# Sheet1.net
KiCad netlist of a schematic drawn in Altium Designer
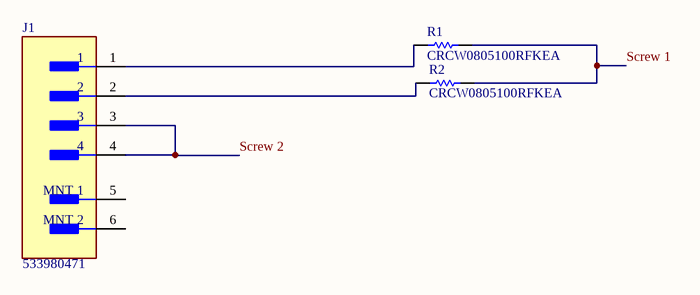
[diagram p0: Sheet1.SchDoc]

(export (version "E")
  (design (tool "Eeschema 10.0.6"))
  (components
    (comp (ref "J1")
      (value "533980471")
      (footprint "FP-533980471-MFG")
      (description "CONN HEADER SMD 4POS 1.25MM")
      (fields
        (field (name "OCTOPART") "https://octopart.com/53398-0471-molex-655296")
        (field (name "MANUFACTURER") "Molex")
      )
      (libsource (lib "Altium Content Vault") (part "3b6f738a5616415d78381ad43816e4a"))
    )
    (comp (ref "R1")
      (value "CRCW0805100RFKEA")
      (footprint "RESC2013X50X30LL20T20")
      (fields (field (name "MANUFACTURER") "Vishay Dale"))
      (libsource (lib "Altium Content Vault") (part "RES"))
    )
    (comp (ref "R2")
      (value "CRCW0805100RFKEA")
      (footprint "RESC2013X50X30LL20T20")
      (fields (field (name "MANUFACTURER") "Vishay Dale"))
      (libsource (lib "Altium Content Vault") (part "RES"))
    )
  )
  (nets
    (net (code "1") (name "/Screw 1") (class "Default")
      (node (ref "R1") (pin "2") (pinfunction "2_2") (pintype "passive"))
      (node (ref "R2") (pin "2") (pinfunction "2_2") (pintype "passive"))
    )
    (net (code "2") (name "/Screw 2") (class "Default")
      (node (ref "J1") (pin "3") (pinfunction "3_3") (pintype "passive"))
      (node (ref "J1") (pin "4") (pinfunction "4_4") (pintype "passive"))
    )
    (net (code "3") (name "Net-(J1-Pad1)") (class "Default")
      (node (ref "J1") (pin "1") (pinfunction "1_1") (pintype "passive"))
      (node (ref "R1") (pin "1") (pinfunction "1_1") (pintype "passive"))
    )
    (net (code "4") (name "Net-(J1-Pad2)") (class "Default")
      (node (ref "J1") (pin "2") (pinfunction "2_2") (pintype "passive"))
      (node (ref "R2") (pin "1") (pinfunction "1_1") (pintype "passive"))
    )
    (net (code "5") (name "unconnected-(J1-MNT_1-Pad5)") (class "Default")
      (node (ref "J1") (pin "5") (pinfunction "MNT_1_5") (pintype "passive"))
    )
    (net (code "6") (name "unconnected-(J1-MNT_2-Pad6)") (class "Default")
      (node (ref "J1") (pin "6") (pinfunction "MNT_2_6") (pintype "passive"))
    )
  )
)
